# Power.net
KiCad netlist of a schematic drawn in Altium Designer
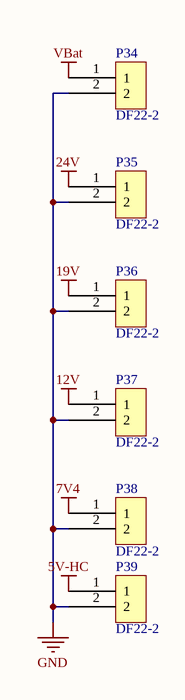
[diagram p0: Power.SchDoc]

(export (version "E")
  (design (tool "Eeschema 10.0.6"))
  (components
    (comp (ref "P34")
      (value "DF22-2")
      (footprint "DF22-2")
      (description "CONN HEADER 2POS 7.92MM PCB TIN")
      (libsource (lib "ControlBoard") (part "DF22-2"))
    )
    (comp (ref "P35")
      (value "DF22-2")
      (footprint "DF63")
      (description "CONN HEADER 2POS 7.92MM PCB TIN")
      (libsource (lib "ControlBoard") (part "DF22-2"))
    )
    (comp (ref "P36")
      (value "DF22-2")
      (footprint "DF63")
      (description "CONN HEADER 2POS 7.92MM PCB TIN")
      (libsource (lib "ControlBoard") (part "DF22-2"))
    )
    (comp (ref "P37")
      (value "DF22-2")
      (footprint "DF63")
      (description "CONN HEADER 2POS 7.92MM PCB TIN")
      (libsource (lib "ControlBoard") (part "DF22-2"))
    )
    (comp (ref "P38")
      (value "DF22-2")
      (footprint "DF63")
      (description "CONN HEADER 2POS 7.92MM PCB TIN")
      (libsource (lib "ControlBoard") (part "DF22-2"))
    )
    (comp (ref "P39")
      (value "DF22-2")
      (footprint "DF63")
      (description "CONN HEADER 2POS 7.92MM PCB TIN")
      (libsource (lib "ControlBoard") (part "DF22-2"))
    )
  )
  (nets
    (net (code "1") (name "5V-HC") (class "Default")
      (node (ref "P39") (pin "1") (pinfunction "1_1") (pintype "passive"))
    )
    (net (code "2") (name "7V4") (class "Default")
      (node (ref "P38") (pin "1") (pinfunction "1_1") (pintype "passive"))
    )
    (net (code "3") (name "12V") (class "Default")
      (node (ref "P37") (pin "1") (pinfunction "1_1") (pintype "passive"))
    )
    (net (code "4") (name "19V") (class "Default")
      (node (ref "P36") (pin "1") (pinfunction "1_1") (pintype "passive"))
    )
    (net (code "5") (name "24V") (class "Default")
      (node (ref "P35") (pin "1") (pinfunction "1_1") (pintype "passive"))
    )
    (net (code "6") (name "GND") (class "Default")
      (node (ref "P34") (pin "2") (pinfunction "2_2") (pintype "passive"))
      (node (ref "P35") (pin "2") (pinfunction "2_2") (pintype "passive"))
      (node (ref "P36") (pin "2") (pinfunction "2_2") (pintype "passive"))
      (node (ref "P37") (pin "2") (pinfunction "2_2") (pintype "passive"))
      (node (ref "P38") (pin "2") (pinfunction "2_2") (pintype "passive"))
      (node (ref "P39") (pin "2") (pinfunction "2_2") (pintype "passive"))
    )
    (net (code "7") (name "VBat") (class "Default")
      (node (ref "P34") (pin "1") (pinfunction "1_1") (pintype "passive"))
    )
  )
)
